# ChargeControllerRevA.net
KiCad netlist of a schematic drawn in EAGLE
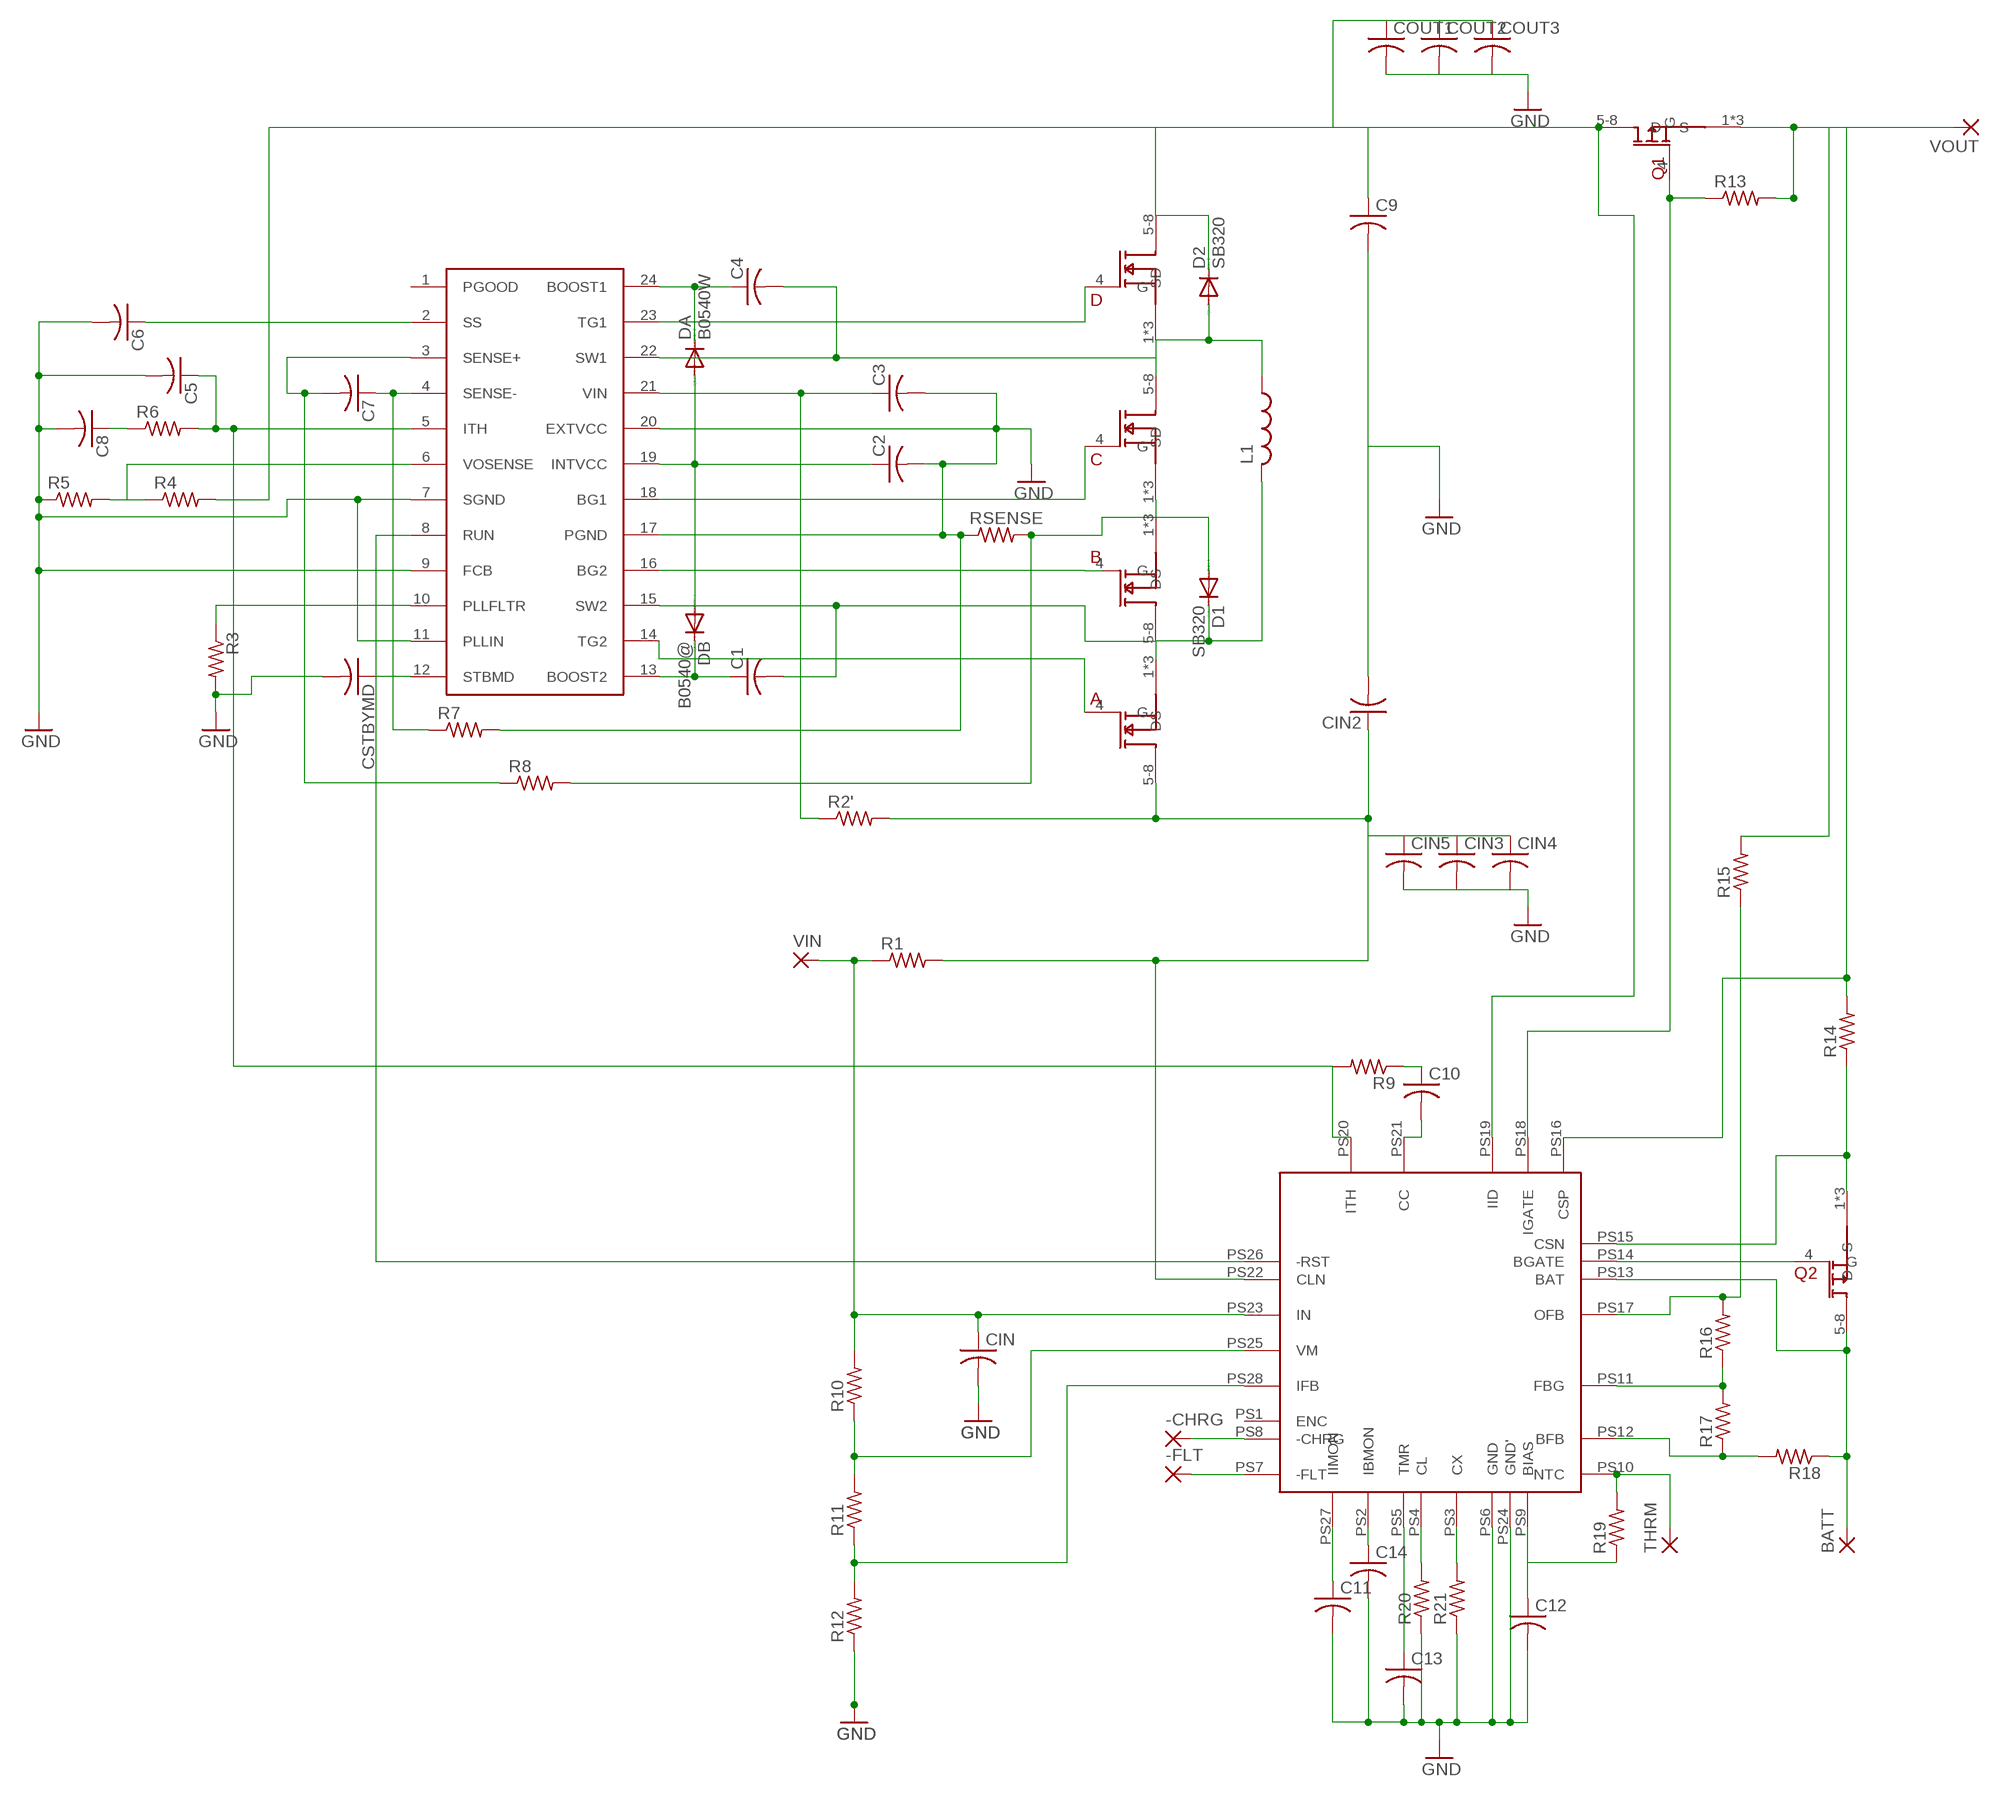
[diagram p0: schematic, sheet 1]

(export (version "E")
  (design (tool "Eeschema 10.0.6"))
  (components
    (comp (ref "-CHRG")
      (value "3,81/1,4")
      (footprint "eagle-import:3,81_1,4")
      (libsource (lib "eagle-import") (part "3,81/1,4"))
    )
    (comp (ref "-FLT")
      (value "3,81/1,4")
      (footprint "eagle-import:3,81_1,4")
      (libsource (lib "eagle-import") (part "3,81/1,4"))
    )
    (comp (ref "A")
      (value "SI7884DP")
      (footprint "eagle-import:POWERPAK-SO-08")
      (libsource (lib "eagle-import") (part "SI7884DP"))
    )
    (comp (ref "B")
      (value "SI7884DP")
      (footprint "eagle-import:POWERPAK-SO-08")
      (libsource (lib "eagle-import") (part "SI7884DP"))
    )
    (comp (ref "BATT")
      (value "3,81/1,4")
      (footprint "eagle-import:3,81_1,4")
      (libsource (lib "eagle-import") (part "3,81/1,4"))
    )
    (comp (ref "C")
      (value "SI7884DP")
      (footprint "eagle-import:POWERPAK-SO-08")
      (libsource (lib "eagle-import") (part "SI7884DP"))
    )
    (comp (ref "C1")
      (value "C-US025-050X050")
      (footprint "eagle-import:C025-050X050")
      (libsource (lib "eagle-import") (part "C-US025-050X050"))
    )
    (comp (ref "C2")
      (value "C-US025-050X050")
      (footprint "eagle-import:C025-050X050")
      (libsource (lib "eagle-import") (part "C-US025-050X050"))
    )
    (comp (ref "C3")
      (value "C-US025-050X050")
      (footprint "eagle-import:C025-050X050")
      (libsource (lib "eagle-import") (part "C-US025-050X050"))
    )
    (comp (ref "C4")
      (value "C-US025-050X050")
      (footprint "eagle-import:C025-050X050")
      (libsource (lib "eagle-import") (part "C-US025-050X050"))
    )
    (comp (ref "C5")
      (value "C-US025-050X050")
      (footprint "eagle-import:C025-050X050")
      (libsource (lib "eagle-import") (part "C-US025-050X050"))
    )
    (comp (ref "C6")
      (value "C-US025-050X050")
      (footprint "eagle-import:C025-050X050")
      (libsource (lib "eagle-import") (part "C-US025-050X050"))
    )
    (comp (ref "C7")
      (value "C-US025-050X050")
      (footprint "eagle-import:C025-050X050")
      (libsource (lib "eagle-import") (part "C-US025-050X050"))
    )
    (comp (ref "C8")
      (value "C-US025-050X050")
      (footprint "eagle-import:C025-050X050")
      (libsource (lib "eagle-import") (part "C-US025-050X050"))
    )
    (comp (ref "C9")
      (value "C-US025-050X050")
      (footprint "eagle-import:C025-050X050")
      (libsource (lib "eagle-import") (part "C-US025-050X050"))
    )
    (comp (ref "C10")
      (value "C-US025-050X050")
      (footprint "eagle-import:C025-050X050")
      (libsource (lib "eagle-import") (part "C-US025-050X050"))
    )
    (comp (ref "C11")
      (value "C-US025-050X050")
      (footprint "eagle-import:C025-050X050")
      (libsource (lib "eagle-import") (part "C-US025-050X050"))
    )
    (comp (ref "C12")
      (value "C-US025-050X050")
      (footprint "eagle-import:C025-050X050")
      (libsource (lib "eagle-import") (part "C-US025-050X050"))
    )
    (comp (ref "C13")
      (value "C-US025-050X050")
      (footprint "eagle-import:C025-050X050")
      (libsource (lib "eagle-import") (part "C-US025-050X050"))
    )
    (comp (ref "C14")
      (value "C-US025-050X050")
      (footprint "eagle-import:C025-050X050")
      (libsource (lib "eagle-import") (part "C-US025-050X050"))
    )
    (comp (ref "CIN")
      (value "C-US025-050X050")
      (footprint "eagle-import:C025-050X050")
      (libsource (lib "eagle-import") (part "C-US025-050X050"))
    )
    (comp (ref "CIN2")
      (value "C-US025-050X050")
      (footprint "eagle-import:C025-050X050")
      (libsource (lib "eagle-import") (part "C-US025-050X050"))
    )
    (comp (ref "CIN3")
      (value "C-US025-050X050")
      (footprint "eagle-import:C025-050X050")
      (libsource (lib "eagle-import") (part "C-US025-050X050"))
    )
    (comp (ref "CIN4")
      (value "C-US025-050X050")
      (footprint "eagle-import:C025-050X050")
      (libsource (lib "eagle-import") (part "C-US025-050X050"))
    )
    (comp (ref "CIN5")
      (value "C-US025-050X050")
      (footprint "eagle-import:C025-050X050")
      (libsource (lib "eagle-import") (part "C-US025-050X050"))
    )
    (comp (ref "COUT1")
      (value "C-US025-050X050")
      (footprint "eagle-import:C025-050X050")
      (libsource (lib "eagle-import") (part "C-US025-050X050"))
    )
    (comp (ref "COUT2")
      (value "C-US025-050X050")
      (footprint "eagle-import:C025-050X050")
      (libsource (lib "eagle-import") (part "C-US025-050X050"))
    )
    (comp (ref "COUT3")
      (value "C-US025-050X050")
      (footprint "eagle-import:C025-050X050")
      (libsource (lib "eagle-import") (part "C-US025-050X050"))
    )
    (comp (ref "CSTBYMD")
      (value "C-US025-050X050")
      (footprint "eagle-import:C025-050X050")
      (libsource (lib "eagle-import") (part "C-US025-050X050"))
    )
    (comp (ref "D")
      (value "SI7884DP")
      (footprint "eagle-import:POWERPAK-SO-08")
      (libsource (lib "eagle-import") (part "SI7884DP"))
    )
    (comp (ref "D1")
      (value "SB320")
      (footprint "eagle-import:DO201-15")
      (libsource (lib "eagle-import") (part "SB320"))
    )
    (comp (ref "D2")
      (value "SB320")
      (footprint "eagle-import:DO201-15")
      (libsource (lib "eagle-import") (part "SB320"))
    )
    (comp (ref "DA")
      (value "B0540W")
      (footprint "eagle-import:SOD123")
      (libsource (lib "eagle-import") (part "MBR0520LT"))
    )
    (comp (ref "DB")
      (value "B0540@")
      (footprint "eagle-import:SOD123")
      (libsource (lib "eagle-import") (part "MBR0520LT"))
    )
    (comp (ref "L1")
      (value "L-US6000-XXX-RC")
      (footprint "eagle-import:6000-XXXX-RC")
      (libsource (lib "eagle-import") (part "L-US6000-XXX-RC"))
    )
    (comp (ref "Q1")
      (value "SI7135DP")
      (footprint "eagle-import:POWERPAK-SO-08")
      (libsource (lib "eagle-import") (part "SI7135DP"))
    )
    (comp (ref "Q2")
      (value "SI7135DP")
      (footprint "eagle-import:POWERPAK-SO-08")
      (libsource (lib "eagle-import") (part "SI7135DP"))
    )
    (comp (ref "R1")
      (value "R-US_0309/12")
      (footprint "eagle-import:0309_12")
      (libsource (lib "eagle-import") (part "R-US_0309/12"))
    )
    (comp (ref "R2'")
      (value "R-US_0309/12")
      (footprint "eagle-import:0309_12")
      (libsource (lib "eagle-import") (part "R-US_0309/12"))
    )
    (comp (ref "R3")
      (value "R-US_0309/12")
      (footprint "eagle-import:0309_12")
      (libsource (lib "eagle-import") (part "R-US_0309/12"))
    )
    (comp (ref "R4")
      (value "R-US_0309/12")
      (footprint "eagle-import:0309_12")
      (libsource (lib "eagle-import") (part "R-US_0309/12"))
    )
    (comp (ref "R5")
      (value "R-US_0309/12")
      (footprint "eagle-import:0309_12")
      (libsource (lib "eagle-import") (part "R-US_0309/12"))
    )
    (comp (ref "R6")
      (value "R-US_0309/12")
      (footprint "eagle-import:0309_12")
      (libsource (lib "eagle-import") (part "R-US_0309/12"))
    )
    (comp (ref "R7")
      (value "R-US_0309/12")
      (footprint "eagle-import:0309_12")
      (libsource (lib "eagle-import") (part "R-US_0309/12"))
    )
    (comp (ref "R8")
      (value "R-US_0309/12")
      (footprint "eagle-import:0309_12")
      (libsource (lib "eagle-import") (part "R-US_0309/12"))
    )
    (comp (ref "R9")
      (value "R-US_0309/12")
      (footprint "eagle-import:0309_12")
      (libsource (lib "eagle-import") (part "R-US_0309/12"))
    )
    (comp (ref "R10")
      (value "R-US_0309/12")
      (footprint "eagle-import:0309_12")
      (libsource (lib "eagle-import") (part "R-US_0309/12"))
    )
    (comp (ref "R11")
      (value "R-US_0309/12")
      (footprint "eagle-import:0309_12")
      (libsource (lib "eagle-import") (part "R-US_0309/12"))
    )
    (comp (ref "R12")
      (value "R-US_0309/12")
      (footprint "eagle-import:0309_12")
      (libsource (lib "eagle-import") (part "R-US_0309/12"))
    )
    (comp (ref "R13")
      (value "R-US_0309/12")
      (footprint "eagle-import:0309_12")
      (libsource (lib "eagle-import") (part "R-US_0309/12"))
    )
    (comp (ref "R14")
      (value "R-US_0309/12")
      (footprint "eagle-import:0309_12")
      (libsource (lib "eagle-import") (part "R-US_0309/12"))
    )
    (comp (ref "R15")
      (value "R-US_0309/12")
      (footprint "eagle-import:0309_12")
      (libsource (lib "eagle-import") (part "R-US_0309/12"))
    )
    (comp (ref "R16")
      (value "R-US_0309/12")
      (footprint "eagle-import:0309_12")
      (libsource (lib "eagle-import") (part "R-US_0309/12"))
    )
    (comp (ref "R17")
      (value "R-US_0309/12")
      (footprint "eagle-import:0309_12")
      (libsource (lib "eagle-import") (part "R-US_0309/12"))
    )
    (comp (ref "R18")
      (value "R-US_0309/12")
      (footprint "eagle-import:0309_12")
      (libsource (lib "eagle-import") (part "R-US_0309/12"))
    )
    (comp (ref "R19")
      (value "R-US_0309/12")
      (footprint "eagle-import:0309_12")
      (libsource (lib "eagle-import") (part "R-US_0309/12"))
    )
    (comp (ref "R20")
      (value "R-US_0309/12")
      (footprint "eagle-import:0309_12")
      (libsource (lib "eagle-import") (part "R-US_0309/12"))
    )
    (comp (ref "R21")
      (value "R-US_0309/12")
      (footprint "eagle-import:0309_12")
      (libsource (lib "eagle-import") (part "R-US_0309/12"))
    )
    (comp (ref "RSENSE")
      (value "R-US_0309/12")
      (footprint "eagle-import:0309_12")
      (libsource (lib "eagle-import") (part "R-US_0309/12"))
    )
    (comp (ref "THRM")
      (value "3,81/1,4")
      (footprint "eagle-import:3,81_1,4")
      (libsource (lib "eagle-import") (part "3,81/1,4"))
    )
    (comp (ref "U$1")
      (value "LT3780")
      (footprint "eagle-import:SSOP24")
      (libsource (lib "eagle-import") (part "LT3780"))
    )
    (comp (ref "U$2")
      (value "LTC4000-1")
      (footprint "eagle-import:SSOP-28_GN")
      (libsource (lib "eagle-import") (part "LTC4000-1(B)GN"))
    )
    (comp (ref "VIN")
      (value "3,81/1,4")
      (footprint "eagle-import:3,81_1,4")
      (libsource (lib "eagle-import") (part "3,81/1,4"))
    )
    (comp (ref "VOUT")
      (value "3,81/1,4")
      (footprint "eagle-import:3,81_1,4")
      (libsource (lib "eagle-import") (part "3,81/1,4"))
    )
  )
  (nets
    (net (code "1") (name "GND") (class "Default")
      (node (ref "C11") (pin "2") (pinfunction "2_2") (pintype "passive"))
      (node (ref "C12") (pin "2") (pinfunction "2_2") (pintype "passive"))
      (node (ref "C13") (pin "2") (pinfunction "2_2") (pintype "passive"))
      (node (ref "C14") (pin "2") (pinfunction "2_2") (pintype "passive"))
      (node (ref "C2") (pin "2") (pinfunction "2_2") (pintype "passive"))
      (node (ref "C3") (pin "2") (pinfunction "2_2") (pintype "passive"))
      (node (ref "C5") (pin "2") (pinfunction "2_2") (pintype "passive"))
      (node (ref "C6") (pin "2") (pinfunction "2_2") (pintype "passive"))
      (node (ref "C8") (pin "2") (pinfunction "2_2") (pintype "passive"))
      (node (ref "C9") (pin "2") (pinfunction "2_2") (pintype "passive"))
      (node (ref "CIN") (pin "2") (pinfunction "2_2") (pintype "passive"))
      (node (ref "CIN2") (pin "2") (pinfunction "2_2") (pintype "passive"))
      (node (ref "CIN3") (pin "2") (pinfunction "2_2") (pintype "passive"))
      (node (ref "CIN4") (pin "2") (pinfunction "2_2") (pintype "passive"))
      (node (ref "CIN5") (pin "2") (pinfunction "2_2") (pintype "passive"))
      (node (ref "COUT1") (pin "2") (pinfunction "2_2") (pintype "passive"))
      (node (ref "COUT2") (pin "2") (pinfunction "2_2") (pintype "passive"))
      (node (ref "COUT3") (pin "2") (pinfunction "2_2") (pintype "passive"))
      (node (ref "CSTBYMD") (pin "2") (pinfunction "2_2") (pintype "passive"))
      (node (ref "R12") (pin "1") (pinfunction "1_1") (pintype "passive"))
      (node (ref "R20") (pin "1") (pinfunction "1_1") (pintype "passive"))
      (node (ref "R21") (pin "1") (pinfunction "1_1") (pintype "passive"))
      (node (ref "R3") (pin "2") (pinfunction "2_2") (pintype "passive"))
      (node (ref "R5") (pin "1") (pinfunction "1_1") (pintype "passive"))
      (node (ref "R7") (pin "2") (pinfunction "2_2") (pintype "passive"))
      (node (ref "RSENSE") (pin "1") (pinfunction "1_1") (pintype "passive"))
      (node (ref "U$1") (pin "11") (pinfunction "PLLIN_11") (pintype "bidirectional"))
      (node (ref "U$1") (pin "17") (pinfunction "PGND_17") (pintype "bidirectional"))
      (node (ref "U$1") (pin "20") (pinfunction "EXTVCC_20") (pintype "bidirectional"))
      (node (ref "U$1") (pin "7") (pinfunction "SGND_7") (pintype "bidirectional"))
      (node (ref "U$1") (pin "9") (pinfunction "FCB_9") (pintype "bidirectional"))
      (node (ref "U$2") (pin "PS24") (pinfunction "GND'_PS24") (pintype "bidirectional"))
      (node (ref "U$2") (pin "PS6") (pinfunction "GND_PS6") (pintype "bidirectional"))
    )
    (net (code "2") (name "Net-(-CHRG-P)") (class "Default")
      (node (ref "-CHRG") (pin "1") (pinfunction "P_1") (pintype "passive"))
      (node (ref "U$2") (pin "PS8") (pinfunction "-CHRG_PS8") (pintype "bidirectional"))
    )
    (net (code "3") (name "Net-(-FLT-P)") (class "Default")
      (node (ref "-FLT") (pin "1") (pinfunction "P_1") (pintype "passive"))
      (node (ref "U$2") (pin "PS7") (pinfunction "-FLT_PS7") (pintype "bidirectional"))
    )
    (net (code "4") (name "Net-(A-D)") (class "Default")
      (node (ref "A") (pin "5-8") (pinfunction "D_5-8") (pintype "bidirectional"))
      (node (ref "CIN2") (pin "1") (pinfunction "1_1") (pintype "passive"))
      (node (ref "CIN3") (pin "1") (pinfunction "1_1") (pintype "passive"))
      (node (ref "CIN4") (pin "1") (pinfunction "1_1") (pintype "passive"))
      (node (ref "CIN5") (pin "1") (pinfunction "1_1") (pintype "passive"))
      (node (ref "R1") (pin "2") (pinfunction "2_2") (pintype "passive"))
      (node (ref "R2'") (pin "2") (pinfunction "2_2") (pintype "passive"))
      (node (ref "U$2") (pin "PS22") (pinfunction "CLN_PS22") (pintype "bidirectional"))
    )
    (net (code "5") (name "Net-(A-G)") (class "Default")
      (node (ref "A") (pin "4") (pinfunction "G_4") (pintype "bidirectional"))
      (node (ref "U$1") (pin "14") (pinfunction "TG2_14") (pintype "bidirectional"))
    )
    (net (code "6") (name "Net-(B-D)") (class "Default")
      (node (ref "A") (pin "1") (pinfunction "S_1") (pintype "bidirectional"))
      (node (ref "A") (pin "2") (pinfunction "S_2") (pintype "bidirectional"))
      (node (ref "A") (pin "3") (pinfunction "S_3") (pintype "bidirectional"))
      (node (ref "B") (pin "5-8") (pinfunction "D_5-8") (pintype "bidirectional"))
      (node (ref "C1") (pin "2") (pinfunction "2_2") (pintype "passive"))
      (node (ref "D1") (pin "C") (pinfunction "C_C") (pintype "passive"))
      (node (ref "L1") (pin "2") (pinfunction "2_2") (pintype "passive"))
      (node (ref "U$1") (pin "15") (pinfunction "SW2_15") (pintype "bidirectional"))
    )
    (net (code "7") (name "Net-(B-G)") (class "Default")
      (node (ref "B") (pin "4") (pinfunction "G_4") (pintype "bidirectional"))
      (node (ref "U$1") (pin "16") (pinfunction "BG2_16") (pintype "bidirectional"))
    )
    (net (code "8") (name "Net-(B-S-Pad1)") (class "Default")
      (node (ref "B") (pin "1") (pinfunction "S_1") (pintype "bidirectional"))
      (node (ref "B") (pin "2") (pinfunction "S_2") (pintype "bidirectional"))
      (node (ref "B") (pin "3") (pinfunction "S_3") (pintype "bidirectional"))
      (node (ref "C") (pin "1") (pinfunction "S_1") (pintype "bidirectional"))
      (node (ref "C") (pin "2") (pinfunction "S_2") (pintype "bidirectional"))
      (node (ref "C") (pin "3") (pinfunction "S_3") (pintype "bidirectional"))
      (node (ref "D1") (pin "A") (pinfunction "A_A") (pintype "passive"))
      (node (ref "R8") (pin "2") (pinfunction "2_2") (pintype "passive"))
      (node (ref "RSENSE") (pin "2") (pinfunction "2_2") (pintype "passive"))
    )
    (net (code "9") (name "Net-(BATT-P)") (class "Default")
      (node (ref "BATT") (pin "1") (pinfunction "P_1") (pintype "passive"))
      (node (ref "Q2") (pin "5-8") (pinfunction "D_5-8") (pintype "bidirectional"))
      (node (ref "R18") (pin "1") (pinfunction "1_1") (pintype "passive"))
      (node (ref "U$2") (pin "PS13") (pinfunction "BAT_PS13") (pintype "bidirectional"))
    )
    (net (code "10") (name "Net-(C-D)") (class "Default")
      (node (ref "C") (pin "5-8") (pinfunction "D_5-8") (pintype "bidirectional"))
      (node (ref "C4") (pin "2") (pinfunction "2_2") (pintype "passive"))
      (node (ref "D") (pin "1") (pinfunction "S_1") (pintype "bidirectional"))
      (node (ref "D") (pin "2") (pinfunction "S_2") (pintype "bidirectional"))
      (node (ref "D") (pin "3") (pinfunction "S_3") (pintype "bidirectional"))
      (node (ref "D2") (pin "A") (pinfunction "A_A") (pintype "passive"))
      (node (ref "L1") (pin "1") (pinfunction "1_1") (pintype "passive"))
      (node (ref "U$1") (pin "22") (pinfunction "SW1_22") (pintype "bidirectional"))
    )
    (net (code "11") (name "Net-(C-G)") (class "Default")
      (node (ref "C") (pin "4") (pinfunction "G_4") (pintype "bidirectional"))
      (node (ref "U$1") (pin "18") (pinfunction "BG1_18") (pintype "bidirectional"))
    )
    (net (code "12") (name "Net-(C8-Pad1)") (class "Default")
      (node (ref "C8") (pin "1") (pinfunction "1_1") (pintype "passive"))
      (node (ref "R6") (pin "1") (pinfunction "1_1") (pintype "passive"))
    )
    (net (code "13") (name "Net-(C10-Pad1)") (class "Default")
      (node (ref "C10") (pin "1") (pinfunction "1_1") (pintype "passive"))
      (node (ref "R9") (pin "1") (pinfunction "1_1") (pintype "passive"))
    )
    (net (code "14") (name "Net-(D-D)") (class "Default")
      (node (ref "C9") (pin "1") (pinfunction "1_1") (pintype "passive"))
      (node (ref "COUT1") (pin "1") (pinfunction "1_1") (pintype "passive"))
      (node (ref "COUT2") (pin "1") (pinfunction "1_1") (pintype "passive"))
      (node (ref "COUT3") (pin "1") (pinfunction "1_1") (pintype "passive"))
      (node (ref "D") (pin "5-8") (pinfunction "D_5-8") (pintype "bidirectional"))
      (node (ref "D2") (pin "C") (pinfunction "C_C") (pintype "passive"))
      (node (ref "Q1") (pin "5-8") (pinfunction "D_5-8") (pintype "bidirectional"))
      (node (ref "R4") (pin "2") (pinfunction "2_2") (pintype "passive"))
      (node (ref "U$2") (pin "PS19") (pinfunction "IID_PS19") (pintype "bidirectional"))
    )
    (net (code "15") (name "Net-(D-G)") (class "Default")
      (node (ref "D") (pin "4") (pinfunction "G_4") (pintype "bidirectional"))
      (node (ref "U$1") (pin "23") (pinfunction "TG1_23") (pintype "bidirectional"))
    )
    (net (code "16") (name "Net-(Q1-G)") (class "Default")
      (node (ref "Q1") (pin "4") (pinfunction "G_4") (pintype "bidirectional"))
      (node (ref "R13") (pin "1") (pinfunction "1_1") (pintype "passive"))
      (node (ref "U$2") (pin "PS18") (pinfunction "IGATE_PS18") (pintype "bidirectional"))
    )
    (net (code "17") (name "Net-(Q2-G)") (class "Default")
      (node (ref "Q2") (pin "4") (pinfunction "G_4") (pintype "bidirectional"))
      (node (ref "U$2") (pin "PS14") (pinfunction "BGATE_PS14") (pintype "bidirectional"))
    )
    (net (code "18") (name "Net-(THRM-P)") (class "Default")
      (node (ref "R19") (pin "2") (pinfunction "2_2") (pintype "passive"))
      (node (ref "THRM") (pin "1") (pinfunction "P_1") (pintype "passive"))
      (node (ref "U$2") (pin "PS10") (pinfunction "NTC_PS10") (pintype "bidirectional"))
    )
    (net (code "19") (name "Net-(U$1-BOOST1)") (class "Default")
      (node (ref "C4") (pin "1") (pinfunction "1_1") (pintype "passive"))
      (node (ref "DA") (pin "C") (pinfunction "C_C") (pintype "passive"))
      (node (ref "U$1") (pin "24") (pinfunction "BOOST1_24") (pintype "bidirectional"))
    )
    (net (code "20") (name "Net-(U$1-BOOST2)") (class "Default")
      (node (ref "C1") (pin "1") (pinfunction "1_1") (pintype "passive"))
      (node (ref "DB") (pin "C") (pinfunction "C_C") (pintype "passive"))
      (node (ref "U$1") (pin "13") (pinfunction "BOOST2_13") (pintype "bidirectional"))
    )
    (net (code "21") (name "Net-(U$1-INTVCC)") (class "Default")
      (node (ref "C2") (pin "1") (pinfunction "1_1") (pintype "passive"))
      (node (ref "DA") (pin "A") (pinfunction "A_A") (pintype "passive"))
      (node (ref "DB") (pin "A") (pinfunction "A_A") (pintype "passive"))
      (node (ref "U$1") (pin "19") (pinfunction "INTVCC_19") (pintype "bidirectional"))
    )
    (net (code "22") (name "Net-(U$1-ITH)") (class "Default")
      (node (ref "C5") (pin "1") (pinfunction "1_1") (pintype "passive"))
      (node (ref "R6") (pin "2") (pinfunction "2_2") (pintype "passive"))
      (node (ref "R9") (pin "2") (pinfunction "2_2") (pintype "passive"))
      (node (ref "U$1") (pin "5") (pinfunction "ITH_5") (pintype "bidirectional"))
      (node (ref "U$2") (pin "PS20") (pinfunction "ITH_PS20") (pintype "bidirectional"))
    )
    (net (code "23") (name "Net-(U$1-PLLFLTR)") (class "Default")
      (node (ref "R3") (pin "1") (pinfunction "1_1") (pintype "passive"))
      (node (ref "U$1") (pin "10") (pinfunction "PLLFLTR_10") (pintype "bidirectional"))
    )
    (net (code "24") (name "Net-(U$1-RUN)") (class "Default")
      (node (ref "U$1") (pin "8") (pinfunction "RUN_8") (pintype "bidirectional"))
      (node (ref "U$2") (pin "PS26") (pinfunction "-RST_PS26") (pintype "bidirectional"))
    )
    (net (code "25") (name "Net-(U$1-SENSE+)") (class "Default")
      (node (ref "C7") (pin "2") (pinfunction "2_2") (pintype "passive"))
      (node (ref "R8") (pin "1") (pinfunction "1_1") (pintype "passive"))
      (node (ref "U$1") (pin "3") (pinfunction "SENSE+_3") (pintype "bidirectional"))
    )
    (net (code "26") (name "Net-(U$1-SENSE-)") (class "Default")
      (node (ref "C7") (pin "1") (pinfunction "1_1") (pintype "passive"))
      (node (ref "R7") (pin "1") (pinfunction "1_1") (pintype "passive"))
      (node (ref "U$1") (pin "4") (pinfunction "SENSE-_4") (pintype "bidirectional"))
    )
    (net (code "27") (name "Net-(U$1-SS)") (class "Default")
      (node (ref "C6") (pin "1") (pinfunction "1_1") (pintype "passive"))
      (node (ref "U$1") (pin "2") (pinfunction "SS_2") (pintype "bidirectional"))
    )
    (net (code "28") (name "Net-(U$1-STBMD)") (class "Default")
      (node (ref "CSTBYMD") (pin "1") (pinfunction "1_1") (pintype "passive"))
      (node (ref "U$1") (pin "12") (pinfunction "STBMD_12") (pintype "bidirectional"))
    )
    (net (code "29") (name "Net-(U$1-VIN)") (class "Default")
      (node (ref "C3") (pin "1") (pinfunction "1_1") (pintype "passive"))
      (node (ref "R2'") (pin "1") (pinfunction "1_1") (pintype "passive"))
      (node (ref "U$1") (pin "21") (pinfunction "VIN_21") (pintype "bidirectional"))
    )
    (net (code "30") (name "Net-(U$1-VOSENSE)") (class "Default")
      (node (ref "R4") (pin "1") (pinfunction "1_1") (pintype "passive"))
      (node (ref "R5") (pin "2") (pinfunction "2_2") (pintype "passive"))
      (node (ref "U$1") (pin "6") (pinfunction "VOSENSE_6") (pintype "bidirectional"))
    )
    (net (code "31") (name "Net-(U$2-BFB)") (class "Default")
      (node (ref "R17") (pin "1") (pinfunction "1_1") (pintype "passive"))
      (node (ref "R18") (pin "2") (pinfunction "2_2") (pintype "passive"))
      (node (ref "U$2") (pin "PS12") (pinfunction "BFB_PS12") (pintype "bidirectional"))
    )
    (net (code "32") (name "Net-(U$2-BIAS)") (class "Default")
      (node (ref "C12") (pin "1") (pinfunction "1_1") (pintype "passive"))
      (node (ref "R19") (pin "1") (pinfunction "1_1") (pintype "passive"))
      (node (ref "U$2") (pin "PS9") (pinfunction "BIAS_PS9") (pintype "bidirectional"))
    )
    (net (code "33") (name "Net-(U$2-CC)") (class "Default")
      (node (ref "C10") (pin "2") (pinfunction "2_2") (pintype "passive"))
      (node (ref "U$2") (pin "PS21") (pinfunction "CC_PS21") (pintype "bidirectional"))
    )
    (net (code "34") (name "Net-(U$2-CL)") (class "Default")
      (node (ref "R20") (pin "2") (pinfunction "2_2") (pintype "passive"))
      (node (ref "U$2") (pin "PS4") (pinfunction "CL_PS4") (pintype "bidirectional"))
    )
    (net (code "35") (name "Net-(U$2-CSN)") (class "Default")
      (node (ref "Q2") (pin "1") (pinfunction "S_1") (pintype "bidirectional"))
      (node (ref "Q2") (pin "2") (pinfunction "S_2") (pintype "bidirectional"))
      (node (ref "Q2") (pin "3") (pinfunction "S_3") (pintype "bidirectional"))
      (node (ref "R14") (pin "1") (pinfunction "1_1") (pintype "passive"))
      (node (ref "U$2") (pin "PS15") (pinfunction "CSN_PS15") (pintype "bidirectional"))
    )
    (net (code "36") (name "Net-(U$2-CSP)") (class "Default")
      (node (ref "Q1") (pin "1") (pinfunction "S_1") (pintype "bidirectional"))
      (node (ref "Q1") (pin "2") (pinfunction "S_2") (pintype "bidirectional"))
      (node (ref "Q1") (pin "3") (pinfunction "S_3") (pintype "bidirectional"))
      (node (ref "R13") (pin "2") (pinfunction "2_2") (pintype "passive"))
      (node (ref "R14") (pin "2") (pinfunction "2_2") (pintype "passive"))
      (node (ref "R15") (pin "2") (pinfunction "2_2") (pintype "passive"))
      (node (ref "U$2") (pin "PS16") (pinfunction "CSP_PS16") (pintype "bidirectional"))
      (node (ref "VOUT") (pin "1") (pinfunction "P_1") (pintype "passive"))
    )
    (net (code "37") (name "Net-(U$2-CX)") (class "Default")
      (node (ref "R21") (pin "2") (pinfunction "2_2") (pintype "passive"))
      (node (ref "U$2") (pin "PS3") (pinfunction "CX_PS3") (pintype "bidirectional"))
    )
    (net (code "38") (name "Net-(U$2-FBG)") (class "Default")
      (node (ref "R16") (pin "1") (pinfunction "1_1") (pintype "passive"))
      (node (ref "R17") (pin "2") (pinfunction "2_2") (pintype "passive"))
      (node (ref "U$2") (pin "PS11") (pinfunction "FBG_PS11") (pintype "bidirectional"))
    )
    (net (code "39") (name "Net-(U$2-IBMON)") (class "Default")
      (node (ref "C14") (pin "1") (pinfunction "1_1") (pintype "passive"))
      (node (ref "U$2") (pin "PS2") (pinfunction "IBMON_PS2") (pintype "bidirectional"))
    )
    (net (code "40") (name "Net-(U$2-IFB)") (class "Default")
      (node (ref "R11") (pin "1") (pinfunction "1_1") (pintype "passive"))
      (node (ref "R12") (pin "2") (pinfunction "2_2") (pintype "passive"))
      (node (ref "U$2") (pin "PS28") (pinfunction "IFB_PS28") (pintype "bidirectional"))
    )
    (net (code "41") (name "Net-(U$2-IIMON)") (class "Default")
      (node (ref "C11") (pin "1") (pinfunction "1_1") (pintype "passive"))
      (node (ref "U$2") (pin "PS27") (pinfunction "IIMON_PS27") (pintype "bidirectional"))
    )
    (net (code "42") (name "Net-(U$2-IN)") (class "Default")
      (node (ref "CIN") (pin "1") (pinfunction "1_1") (pintype "passive"))
      (node (ref "R1") (pin "1") (pinfunction "1_1") (pintype "passive"))
      (node (ref "R10") (pin "2") (pinfunction "2_2") (pintype "passive"))
      (node (ref "U$2") (pin "PS23") (pinfunction "IN_PS23") (pintype "bidirectional"))
      (node (ref "VIN") (pin "1") (pinfunction "P_1") (pintype "passive"))
    )
    (net (code "43") (name "Net-(U$2-OFB)") (class "Default")
      (node (ref "R15") (pin "1") (pinfunction "1_1") (pintype "passive"))
      (node (ref "R16") (pin "2") (pinfunction "2_2") (pintype "passive"))
      (node (ref "U$2") (pin "PS17") (pinfunction "OFB_PS17") (pintype "bidirectional"))
    )
    (net (code "44") (name "Net-(U$2-TMR)") (class "Default")
      (node (ref "C13") (pin "1") (pinfunction "1_1") (pintype "passive"))
      (node (ref "U$2") (pin "PS5") (pinfunction "TMR_PS5") (pintype "bidirectional"))
    )
    (net (code "45") (name "Net-(U$2-VM)") (class "Default")
      (node (ref "R10") (pin "1") (pinfunction "1_1") (pintype "passive"))
      (node (ref "R11") (pin "2") (pinfunction "2_2") (pintype "passive"))
      (node (ref "U$2") (pin "PS25") (pinfunction "VM_PS25") (pintype "bidirectional"))
    )
    (net (code "46") (name "unconnected-(U$1-PGOOD-Pad1)") (class "Default")
      (node (ref "U$1") (pin "1") (pinfunction "PGOOD_1") (pintype "bidirectional"))
    )
    (net (code "47") (name "unconnected-(U$2-ENC-PadPS1)") (class "Default")
      (node (ref "U$2") (pin "PS1") (pinfunction "ENC_PS1") (pintype "bidirectional"))
    )
  )
)
